# LoadCellAmplifierV2.net
KiCad netlist of a schematic drawn in Altium Designer
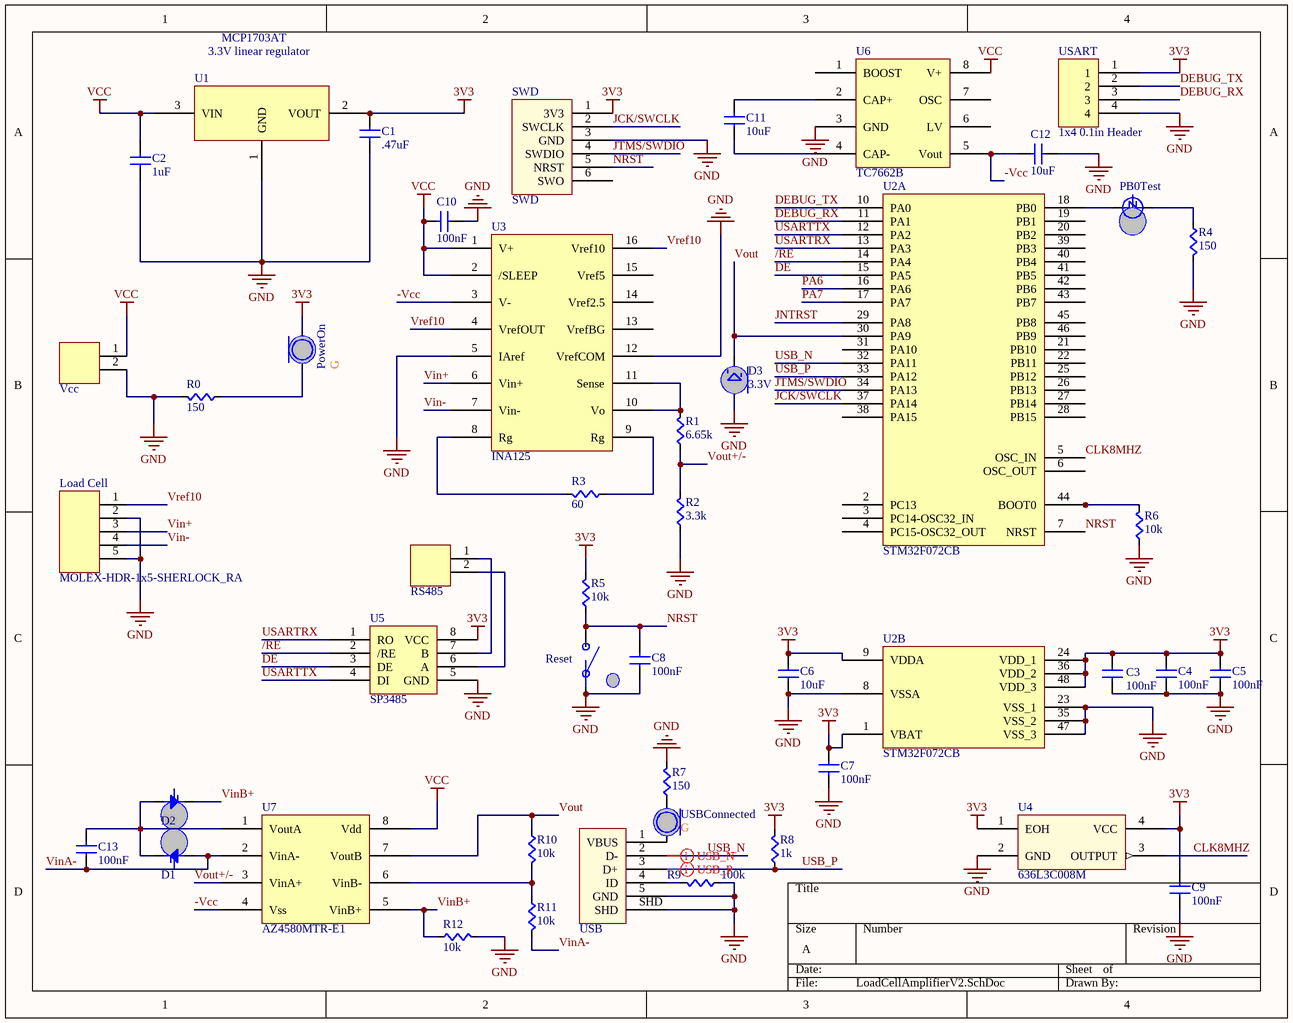
[diagram p0: LoadCellAmplifierV2.SchDoc]

(export (version "E")
  (design (tool "Eeschema 10.0.6"))
  (components
    (comp (ref "C1")
      (value ".47uF")
      (footprint "CAPC0603")
      (fields (field (name "Comment") "Cap"))
      (libsource (lib "SubjuGator8") (part "Cap"))
    )
    (comp (ref "C2")
      (value "1uF")
      (footprint "CAPC0603")
      (fields (field (name "Comment") "Cap"))
      (libsource (lib "SubjuGator8") (part "Cap"))
    )
    (comp (ref "C3")
      (value "100nF")
      (footprint "CAPC0603")
      (fields (field (name "Comment") "Cap"))
      (libsource (lib "SubjuGator8") (part "Cap"))
    )
    (comp (ref "C4")
      (value "100nF")
      (footprint "CAPC0603")
      (fields (field (name "Comment") "Cap"))
      (libsource (lib "SubjuGator8") (part "Cap"))
    )
    (comp (ref "C5")
      (value "100nF")
      (footprint "CAPC0603")
      (fields (field (name "Comment") "Cap"))
      (libsource (lib "SubjuGator8") (part "Cap"))
    )
    (comp (ref "C6")
      (value "10uF")
      (footprint "CAPC1206")
      (fields (field (name "Comment") "Cap"))
      (libsource (lib "SubjuGator8") (part "Cap"))
    )
    (comp (ref "C7")
      (value "100nF")
      (footprint "CAPC0603")
      (fields (field (name "Comment") "Cap"))
      (libsource (lib "SubjuGator8") (part "Cap"))
    )
    (comp (ref "C8")
      (value "100nF")
      (footprint "CAPC0603")
      (fields (field (name "Comment") "Cap"))
      (libsource (lib "SubjuGator8") (part "Cap"))
    )
    (comp (ref "C9")
      (value "100nF")
      (footprint "CAPC0603")
      (fields (field (name "Comment") "Cap"))
      (libsource (lib "SubjuGator8") (part "Cap"))
    )
    (comp (ref "C10")
      (value "100nF")
      (footprint "CAPC0603")
      (fields (field (name "Comment") "Cap"))
      (libsource (lib "SubjuGator8") (part "Cap"))
    )
    (comp (ref "C11")
      (value "10uF")
      (footprint "CAPC1206")
      (fields (field (name "Comment") "Cap"))
      (libsource (lib "SubjuGator8") (part "Cap"))
    )
    (comp (ref "C12")
      (value "10uF")
      (footprint "CAPC1206")
      (fields (field (name "Comment") "Cap"))
      (libsource (lib "SubjuGator8") (part "Cap"))
    )
    (comp (ref "C13")
      (value "100nF")
      (footprint "CAPC0603")
      (fields (field (name "Comment") "Cap"))
      (libsource (lib "SubjuGator8") (part "Cap"))
    )
    (comp (ref "D1")
      (value "Diode")
      (footprint "SOD-323F")
      (description "Standard Diode Template")
      (libsource (lib "SubjuGator8") (part "Diode"))
    )
    (comp (ref "D2")
      (value "Diode")
      (footprint "SOD-323F")
      (description "Standard Diode Template")
      (libsource (lib "") (part "Diode_1"))
    )
    (comp (ref "D3")
      (value "Zener")
      (footprint "LED0603")
      (description "Zener Diode")
      (fields (field (name "ZENER VOLTAGE") "3.3V"))
      (libsource (lib "SubjuGator8") (part "Zener"))
    )
    (comp (ref "Load Cell")
      (value "MOLEX-HDR-1x5-SHERLOCK_RA")
      (footprint "MOLEX-HDR-1X5-SHERLOCK- RA")
      (fields (field (name "MANUFACTURER PART NUMBER") "0353630560") (field (name "MANUFACTURER") "Molex"))
      (libsource (lib "SubjuGator8") (part "MOLEX-HDR-1x5-SHERLOCK_RA"))
    )
    (comp (ref "PB0Test")
      (value "LED")
      (footprint "LED0805")
      (fields (field (name "COLOR") "G"))
      (libsource (lib "SubjuGator8") (part "LED"))
    )
    (comp (ref "PowerOn")
      (value "LED")
      (footprint "LED0805")
      (fields (field (name "COLOR") "G"))
      (libsource (lib "") (part "LED_2"))
    )
    (comp (ref "R0")
      (value "150")
      (footprint "RES0603")
      (fields (field (name "Comment") "Res"))
      (libsource (lib "SubjuGator8") (part "Res"))
    )
    (comp (ref "R1")
      (value "6.65k")
      (footprint "RES0603")
      (fields (field (name "Comment") "Res"))
      (libsource (lib "SubjuGator8") (part "Res"))
    )
    (comp (ref "R2")
      (value "3.3k")
      (footprint "RES0603")
      (fields (field (name "Comment") "Res"))
      (libsource (lib "SubjuGator8") (part "Res"))
    )
    (comp (ref "R3")
      (value "60")
      (footprint "RES0603")
      (fields (field (name "Comment") "Res"))
      (libsource (lib "SubjuGator8") (part "Res"))
    )
    (comp (ref "R4")
      (value "150")
      (footprint "RES0603")
      (fields (field (name "Comment") "Res"))
      (libsource (lib "SubjuGator8") (part "Res"))
    )
    (comp (ref "R5")
      (value "10k")
      (footprint "RES0603")
      (fields (field (name "Comment") "Res"))
      (libsource (lib "SubjuGator8") (part "Res"))
    )
    (comp (ref "R6")
      (value "10k")
      (footprint "RES0603")
      (fields (field (name "Comment") "Res"))
      (libsource (lib "SubjuGator8") (part "Res"))
    )
    (comp (ref "R7")
      (value "150")
      (footprint "RES0603")
      (fields (field (name "Comment") "Res"))
      (libsource (lib "SubjuGator8") (part "Res"))
    )
    (comp (ref "R8")
      (value "1k")
      (footprint "RES0603")
      (fields (field (name "Comment") "Res"))
      (libsource (lib "SubjuGator8") (part "Res"))
    )
    (comp (ref "R9")
      (value "100k")
      (footprint "RES0603")
      (fields (field (name "Comment") "Res"))
      (libsource (lib "SubjuGator8") (part "Res"))
    )
    (comp (ref "R10")
      (value "10k")
      (footprint "RES0603")
      (fields (field (name "Comment") "Res"))
      (libsource (lib "SubjuGator8") (part "Res"))
    )
    (comp (ref "R11")
      (value "10k")
      (footprint "RES0603")
      (fields (field (name "Comment") "Res"))
      (libsource (lib "SubjuGator8") (part "Res"))
    )
    (comp (ref "R12")
      (value "10k")
      (footprint "RES0603")
      (fields (field (name "Comment") "Res"))
      (libsource (lib "SubjuGator8") (part "Res"))
    )
    (comp (ref "Reset")
      (value "Button")
      (footprint "PTS645xxxxSMTR92")
      (description "SPST Button")
      (libsource (lib "SubjuGator8") (part "Button"))
    )
    (comp (ref "RS485")
      (value "2-pin Horz Sherlock")
      (footprint "MOLEX-HDR-1X2-SHERLOCK-HORZ")
      (fields
        (field (name "MANUFACTURER PART NUMBER") "0353630260")
        (field (name "MANUFACTURER") "Molex Inc")
      )
      (libsource (lib "SubjuGator8") (part "MOLEX-HDR-1x2-SHERLOCK_RA"))
    )
    (comp (ref "SWD")
      (value "SWD")
      (footprint "SWD_STM32")
      (description "SWD connector matching the pinout on STM Discovery Boards")
      (libsource (lib "SubjuGator8") (part "SWD_STM32"))
    )
    (comp (ref "U1")
      (value "MCP1703AT")
      (footprint "MCP1703AT-xx02EDB")
      (description "250 mA, 16V, Low Quiescent Current LDO Regulator")
      (libsource (lib "SubjuGator8") (part "MCP1703AT"))
    )
    (comp (ref "U2")
      (value "STM32F072CB")
      (footprint "STM32F072CB")
      (description "MCU 32BIT 128KB FLASH 48LQFP")
      (libsource (lib "ICs") (part "STM32F072CB"))
    )
    (comp (ref "U3")
      (value "INA125")
      (footprint "SOIC127P600X175-16N")
      (description "Instrumentation Amplifier")
      (libsource (lib "ICs") (part "INA125"))
    )
    (comp (ref "U4")
      (value "636L3C008M")
      (footprint "636L3C")
      (description "HCMOS/TTL Clock Oscillator")
      (libsource (lib "SubjuGator8") (part "636L3C"))
    )
    (comp (ref "U5")
      (value "SP3485")
      (footprint "SP3485")
      (description "IC TXRX RS485 HALF DUPLEX 8NSOIC")
      (libsource (lib "SubjuGator8") (part "SP3485"))
    )
    (comp (ref "U6")
      (value "TC7662B")
      (footprint "8-SOIC")
      (description "Charge Pump DC to DC Voltage Converter")
      (libsource (lib "SubjuGator8") (part "TC7662B"))
    )
    (comp (ref "U7")
      (value "AZ4580MTR-E1")
      (footprint "8-SOIC")
      (description "IC OPAMP GEN PURP SO-8")
      (libsource (lib "SubjuGator8") (part "AZ4580MTR-E1"))
    )
    (comp (ref "USART")
      (value "1x4 0.1in Header")
      (footprint "1x4 0.1in Header")
      (libsource (lib "SubjuGator8") (part "1x4 0.1in Header"))
    )
    (comp (ref "USB")
      (value "USB Micro")
      (footprint "10118192-0001LF")
      (description "USB Mini B Metal Shield SMT")
      (libsource (lib "SubjuGator8") (part "USB Micro"))
    )
    (comp (ref "USBConnected")
      (value "LED")
      (footprint "LED0805")
      (fields (field (name "COLOR") "G"))
      (libsource (lib "") (part "LED_1"))
    )
    (comp (ref "Vcc")
      (value "2-pin Horz Sherlock")
      (footprint "MOLEX-HDR-1X2-SHERLOCK-HORZ")
      (fields
        (field (name "MANUFACTURER PART NUMBER") "0353630260")
        (field (name "MANUFACTURER") "Molex Inc")
      )
      (libsource (lib "SubjuGator8") (part "MOLEX-HDR-1x2-SHERLOCK_RA"))
    )
  )
  (nets
    (net (code "1") (name "/-Vcc") (class "Default")
      (node (ref "C12") (pin "2") (pinfunction "B_2") (pintype "passive"))
      (node (ref "U3") (pin "3") (pinfunction "V-_3") (pintype "passive"))
      (node (ref "U6") (pin "5") (pinfunction "Vout_5") (pintype "passive"))
      (node (ref "U7") (pin "4") (pinfunction "Vss_4") (pintype "passive"))
    )
    (net (code "2") (name "/CLK8MHZ") (class "Default")
      (node (ref "U2") (pin "5") (pinfunction "OSC_IN_5") (pintype "passive"))
      (node (ref "U4") (pin "3") (pinfunction "OUTPUT_3") (pintype "output"))
    )
    (net (code "3") (name "/DE") (class "Default")
      (node (ref "U2") (pin "15") (pinfunction "PA5_15") (pintype "passive"))
      (node (ref "U5") (pin "3") (pinfunction "DE_3") (pintype "passive"))
    )
    (net (code "4") (name "/DEBUG_RX") (class "Default")
      (node (ref "U2") (pin "11") (pinfunction "PA1_11") (pintype "passive"))
      (node (ref "USART") (pin "3") (pinfunction "3_3") (pintype "passive"))
    )
    (net (code "5") (name "/DEBUG_TX") (class "Default")
      (node (ref "U2") (pin "10") (pinfunction "PA0_10") (pintype "passive"))
      (node (ref "USART") (pin "2") (pinfunction "2_2") (pintype "passive"))
    )
    (net (code "6") (name "/JCK{slash}SWCLK") (class "Default")
      (node (ref "SWD") (pin "2") (pinfunction "SWCLK_2") (pintype "passive"))
      (node (ref "U2") (pin "37") (pinfunction "PA14_37") (pintype "passive"))
    )
    (net (code "7") (name "/JNTRST") (class "Default")
      (node (ref "U2") (pin "29") (pinfunction "PA8_29") (pintype "passive"))
    )
    (net (code "8") (name "/JTMS{slash}SWDIO") (class "Default")
      (node (ref "SWD") (pin "4") (pinfunction "SWDIO_4") (pintype "passive"))
      (node (ref "U2") (pin "34") (pinfunction "PA13_34") (pintype "passive"))
    )
    (net (code "9") (name "/NRST") (class "Default")
      (node (ref "C8") (pin "1") (pinfunction "A_1") (pintype "passive"))
      (node (ref "R5") (pin "2") (pinfunction "B_2") (pintype "passive"))
      (node (ref "Reset") (pin "B") (pinfunction "B_B") (pintype "passive"))
      (node (ref "SWD") (pin "5") (pinfunction "NRST_5") (pintype "passive"))
      (node (ref "U2") (pin "7") (pinfunction "NRST_7") (pintype "passive"))
    )
    (net (code "10") (name "/PA6") (class "Default")
      (node (ref "U2") (pin "16") (pinfunction "PA6_16") (pintype "passive"))
    )
    (net (code "11") (name "/PA7") (class "Default")
      (node (ref "U2") (pin "17") (pinfunction "PA7_17") (pintype "passive"))
    )
    (net (code "12") (name "/USARTRX") (class "Default")
      (node (ref "U2") (pin "13") (pinfunction "PA3_13") (pintype "passive"))
      (node (ref "U5") (pin "1") (pinfunction "RO_1") (pintype "passive"))
    )
    (net (code "13") (name "/USARTTX") (class "Default")
      (node (ref "U2") (pin "12") (pinfunction "PA2_12") (pintype "passive"))
      (node (ref "U5") (pin "4") (pinfunction "DI_4") (pintype "passive"))
    )
    (net (code "14") (name "/USB_N") (class "Default")
      (node (ref "U2") (pin "32") (pinfunction "PA11_32") (pintype "passive"))
      (node (ref "USB") (pin "2") (pinfunction "D-_2") (pintype "passive"))
    )
    (net (code "15") (name "/USB_P") (class "Default")
      (node (ref "R8") (pin "2") (pinfunction "B_2") (pintype "passive"))
      (node (ref "U2") (pin "33") (pinfunction "PA12_33") (pintype "passive"))
      (node (ref "USB") (pin "3") (pinfunction "D+_3") (pintype "passive"))
    )
    (net (code "16") (name "/Vin+") (class "Default")
      (node (ref "Load Cell") (pin "3") (pinfunction "3_3") (pintype "passive"))
      (node (ref "U3") (pin "6") (pinfunction "Vin+_6") (pintype "passive"))
    )
    (net (code "17") (name "/Vin-") (class "Default")
      (node (ref "Load Cell") (pin "4") (pinfunction "4_4") (pintype "passive"))
      (node (ref "U3") (pin "7") (pinfunction "Vin-_7") (pintype "passive"))
    )
    (net (code "18") (name "/VinA-") (class "Default")
      (node (ref "C13") (pin "2") (pinfunction "B_2") (pintype "passive"))
      (node (ref "D1") (pin "A") (pinfunction "A_A") (pintype "passive"))
      (node (ref "R11") (pin "1") (pinfunction "A_1") (pintype "passive"))
      (node (ref "U7") (pin "2") (pinfunction "VinA-_2") (pintype "passive"))
    )
    (net (code "19") (name "/VinB+") (class "Default")
      (node (ref "D2") (pin "C") (pinfunction "C_C") (pintype "passive"))
      (node (ref "R12") (pin "2") (pinfunction "B_2") (pintype "passive"))
      (node (ref "U7") (pin "5") (pinfunction "VinB+_5") (pintype "passive"))
    )
    (net (code "20") (name "/Vout") (class "Default")
      (node (ref "D3") (pin "C") (pinfunction "C_C") (pintype "passive"))
      (node (ref "R10") (pin "2") (pinfunction "B_2") (pintype "passive"))
      (node (ref "U2") (pin "30") (pinfunction "PA9_30") (pintype "passive"))
      (node (ref "U7") (pin "7") (pinfunction "VoutB_7") (pintype "passive"))
    )
    (net (code "21") (name "/Vout+{slash}-") (class "Default")
      (node (ref "R1") (pin "2") (pinfunction "B_2") (pintype "passive"))
      (node (ref "R2") (pin "1") (pinfunction "A_1") (pintype "passive"))
      (node (ref "U7") (pin "3") (pinfunction "VinA+_3") (pintype "passive"))
    )
    (net (code "22") (name "/Vref10") (class "Default")
      (node (ref "Load Cell") (pin "1") (pinfunction "1_1") (pintype "passive"))
      (node (ref "U3") (pin "16") (pinfunction "Vref10_16") (pintype "passive"))
      (node (ref "U3") (pin "4") (pinfunction "VrefOUT_4") (pintype "passive"))
    )
    (net (code "23") (name "/{slash}RE") (class "Default")
      (node (ref "U2") (pin "14") (pinfunction "PA4_14") (pintype "passive"))
      (node (ref "U5") (pin "2") (pinfunction "/RE_2") (pintype "passive"))
    )
    (net (code "24") (name "3V3") (class "Default")
      (node (ref "C1") (pin "1") (pinfunction "A_1") (pintype "passive"))
      (node (ref "C3") (pin "1") (pinfunction "A_1") (pintype "passive"))
      (node (ref "C4") (pin "1") (pinfunction "A_1") (pintype "passive"))
      (node (ref "C5") (pin "1") (pinfunction "A_1") (pintype "passive"))
      (node (ref "C6") (pin "2") (pinfunction "B_2") (pintype "passive"))
      (node (ref "C7") (pin "1") (pinfunction "A_1") (pintype "passive"))
      (node (ref "C9") (pin "1") (pinfunction "A_1") (pintype "passive"))
      (node (ref "PowerOn") (pin "A") (pinfunction "A_A") (pintype "passive"))
      (node (ref "R5") (pin "1") (pinfunction "A_1") (pintype "passive"))
      (node (ref "R8") (pin "1") (pinfunction "A_1") (pintype "passive"))
      (node (ref "SWD") (pin "1") (pinfunction "3V3_1") (pintype "passive"))
      (node (ref "U1") (pin "2") (pinfunction "VOUT_2") (pintype "passive"))
      (node (ref "U2") (pin "1") (pinfunction "VBAT_1") (pintype "passive"))
      (node (ref "U2") (pin "24") (pinfunction "VDD_1_24") (pintype "passive"))
      (node (ref "U2") (pin "36") (pinfunction "VDD_2_36") (pintype "passive"))
      (node (ref "U2") (pin "48") (pinfunction "VDD_3_48") (pintype "passive"))
      (node (ref "U2") (pin "9") (pinfunction "VDDA_9") (pintype "passive"))
      (node (ref "U4") (pin "1") (pinfunction "EOH_1") (pintype "passive"))
      (node (ref "U4") (pin "4") (pinfunction "VCC_4") (pintype "power_in"))
      (node (ref "U5") (pin "8") (pinfunction "VCC_8") (pintype "passive"))
      (node (ref "USART") (pin "1") (pinfunction "1_1") (pintype "passive"))
    )
    (net (code "25") (name "GND") (class "Default")
      (node (ref "C1") (pin "2") (pinfunction "B_2") (pintype "passive"))
      (node (ref "C10") (pin "1") (pinfunction "A_1") (pintype "passive"))
      (node (ref "C12") (pin "1") (pinfunction "A_1") (pintype "passive"))
      (node (ref "C2") (pin "2") (pinfunction "B_2") (pintype "passive"))
      (node (ref "C3") (pin "2") (pinfunction "B_2") (pintype "passive"))
      (node (ref "C4") (pin "2") (pinfunction "B_2") (pintype "passive"))
      (node (ref "C5") (pin "2") (pinfunction "B_2") (pintype "passive"))
      (node (ref "C6") (pin "1") (pinfunction "A_1") (pintype "passive"))
      (node (ref "C7") (pin "2") (pinfunction "B_2") (pintype "passive"))
      (node (ref "C8") (pin "2") (pinfunction "B_2") (pintype "passive"))
      (node (ref "C9") (pin "2") (pinfunction "B_2") (pintype "passive"))
      (node (ref "D3") (pin "A") (pinfunction "A_A") (pintype "passive"))
      (node (ref "Load Cell") (pin "2") (pinfunction "2_2") (pintype "passive"))
      (node (ref "Load Cell") (pin "5") (pinfunction "5_5") (pintype "passive"))
      (node (ref "R0") (pin "1") (pinfunction "A_1") (pintype "passive"))
      (node (ref "R12") (pin "1") (pinfunction "A_1") (pintype "passive"))
      (node (ref "R2") (pin "2") (pinfunction "B_2") (pintype "passive"))
      (node (ref "R4") (pin "1") (pinfunction "A_1") (pintype "passive"))
      (node (ref "R6") (pin "2") (pinfunction "B_2") (pintype "passive"))
      (node (ref "R7") (pin "1") (pinfunction "A_1") (pintype "passive"))
      (node (ref "R9") (pin "2") (pinfunction "B_2") (pintype "passive"))
      (node (ref "Reset") (pin "A") (pinfunction "A_A") (pintype "passive"))
      (node (ref "SWD") (pin "3") (pinfunction "GND_3") (pintype "passive"))
      (node (ref "U1") (pin "1") (pinfunction "GND_1") (pintype "power_in"))
      (node (ref "U2") (pin "23") (pinfunction "VSS_1_23") (pintype "passive"))
      (node (ref "U2") (pin "35") (pinfunction "VSS_2_35") (pintype "passive"))
      (node (ref "U2") (pin "47") (pinfunction "VSS_3_47") (pintype "passive"))
      (node (ref "U2") (pin "8") (pinfunction "VSSA_8") (pintype "passive"))
      (node (ref "U3") (pin "12") (pinfunction "VrefCOM_12") (pintype "passive"))
      (node (ref "U3") (pin "5") (pinfunction "IAref_5") (pintype "passive"))
      (node (ref "U4") (pin "2") (pinfunction "GND_2") (pintype "power_in"))
      (node (ref "U5") (pin "5") (pinfunction "GND_5") (pintype "passive"))
      (node (ref "U6") (pin "3") (pinfunction "GND_3") (pintype "passive"))
      (node (ref "USART") (pin "4") (pinfunction "4_4") (pintype "passive"))
      (node (ref "USB") (pin "5") (pinfunction "GND_5") (pintype "passive"))
      (node (ref "USB") (pin "SHD") (pinfunction "SHD_SHD") (pintype "passive"))
      (node (ref "Vcc") (pin "2") (pinfunction "2_2") (pintype "passive"))
    )
    (net (code "26") (name "Net-(C11-A)") (class "Default")
      (node (ref "C11") (pin "1") (pinfunction "A_1") (pintype "passive"))
      (node (ref "U6") (pin "4") (pinfunction "CAP-_4") (pintype "passive"))
    )
    (net (code "27") (name "Net-(C11-B)") (class "Default")
      (node (ref "C11") (pin "2") (pinfunction "B_2") (pintype "passive"))
      (node (ref "U6") (pin "2") (pinfunction "CAP+_2") (pintype "passive"))
    )
    (net (code "28") (name "Net-(C13-A)") (class "Default")
      (node (ref "C13") (pin "1") (pinfunction "A_1") (pintype "passive"))
      (node (ref "D1") (pin "C") (pinfunction "C_C") (pintype "passive"))
      (node (ref "D2") (pin "A") (pinfunction "A_A") (pintype "passive"))
      (node (ref "U7") (pin "1") (pinfunction "VoutA_1") (pintype "passive"))
    )
    (net (code "29") (name "Net-(R0-B)") (class "Default")
      (node (ref "PowerOn") (pin "C") (pinfunction "C_C") (pintype "passive"))
      (node (ref "R0") (pin "2") (pinfunction "B_2") (pintype "passive"))
    )
    (net (code "30") (name "Net-(R1-A)") (class "Default")
      (node (ref "R1") (pin "1") (pinfunction "A_1") (pintype "passive"))
      (node (ref "U3") (pin "10") (pinfunction "Vo_10") (pintype "passive"))
      (node (ref "U3") (pin "11") (pinfunction "Sense_11") (pintype "passive"))
    )
    (net (code "31") (name "Net-(R3-A)") (class "Default")
      (node (ref "R3") (pin "1") (pinfunction "A_1") (pintype "passive"))
      (node (ref "U3") (pin "8") (pinfunction "Rg_8") (pintype "passive"))
    )
    (net (code "32") (name "Net-(R3-B)") (class "Default")
      (node (ref "R3") (pin "2") (pinfunction "B_2") (pintype "passive"))
      (node (ref "U3") (pin "9") (pinfunction "Rg_9") (pintype "passive"))
    )
    (net (code "33") (name "Net-(R4-B)") (class "Default")
      (node (ref "PB0Test") (pin "C") (pinfunction "C_C") (pintype "passive"))
      (node (ref "R4") (pin "2") (pinfunction "B_2") (pintype "passive"))
    )
    (net (code "34") (name "Net-(R6-A)") (class "Default")
      (node (ref "R6") (pin "1") (pinfunction "A_1") (pintype "passive"))
      (node (ref "U2") (pin "44") (pinfunction "BOOT0_44") (pintype "passive"))
    )
    (net (code "35") (name "Net-(R7-B)") (class "Default")
      (node (ref "R7") (pin "2") (pinfunction "B_2") (pintype "passive"))
      (node (ref "USBConnected") (pin "C") (pinfunction "C_C") (pintype "passive"))
    )
    (net (code "36") (name "Net-(R9-A)") (class "Default")
      (node (ref "R9") (pin "1") (pinfunction "A_1") (pintype "passive"))
      (node (ref "USB") (pin "4") (pinfunction "ID_4") (pintype "passive"))
    )
    (net (code "37") (name "Net-(R10-A)") (class "Default")
      (node (ref "R10") (pin "1") (pinfunction "A_1") (pintype "passive"))
      (node (ref "R11") (pin "2") (pinfunction "B_2") (pintype "passive"))
      (node (ref "U7") (pin "6") (pinfunction "VinB-_6") (pintype "passive"))
    )
    (net (code "38") (name "Net-(U2A-PB0)") (class "Default")
      (node (ref "PB0Test") (pin "A") (pinfunction "A_A") (pintype "passive"))
      (node (ref "U2") (pin "18") (pinfunction "PB0_18") (pintype "passive"))
    )
    (net (code "39") (name "Net-(U5-A)") (class "Default")
      (node (ref "RS485") (pin "2") (pinfunction "2_2") (pintype "passive"))
      (node (ref "U5") (pin "6") (pinfunction "A_6") (pintype "passive"))
    )
    (net (code "40") (name "Net-(U5-B)") (class "Default")
      (node (ref "RS485") (pin "1") (pinfunction "1_1") (pintype "passive"))
      (node (ref "U5") (pin "7") (pinfunction "B_7") (pintype "passive"))
    )
    (net (code "41") (name "Net-(USB-VBUS)") (class "Default")
      (node (ref "USB") (pin "1") (pinfunction "VBUS_1") (pintype "passive"))
      (node (ref "USBConnected") (pin "A") (pinfunction "A_A") (pintype "passive"))
    )
    (net (code "42") (name "VCC") (class "Default")
      (node (ref "C10") (pin "2") (pinfunction "B_2") (pintype "passive"))
      (node (ref "C2") (pin "1") (pinfunction "A_1") (pintype "passive"))
      (node (ref "U1") (pin "3") (pinfunction "VIN_3") (pintype "passive"))
      (node (ref "U3") (pin "1") (pinfunction "V+_1") (pintype "passive"))
      (node (ref "U3") (pin "2") (pinfunction "/SLEEP_2") (pintype "passive"))
      (node (ref "U6") (pin "8") (pinfunction "V+_8") (pintype "passive"))
      (node (ref "U7") (pin "8") (pinfunction "Vdd_8") (pintype "passive"))
      (node (ref "Vcc") (pin "1") (pinfunction "1_1") (pintype "passive"))
    )
    (net (code "43") (name "unconnected-(SWD-SWO-Pad6)") (class "Default")
      (node (ref "SWD") (pin "6") (pinfunction "SWO_6") (pintype "passive"))
    )
    (net (code "44") (name "unconnected-(U2A-OSC_OUT-Pad6)") (class "Default")
      (node (ref "U2") (pin "6") (pinfunction "OSC_OUT_6") (pintype "passive"))
    )
    (net (code "45") (name "unconnected-(U2A-PA10-Pad31)") (class "Default")
      (node (ref "U2") (pin "31") (pinfunction "PA10_31") (pintype "passive"))
    )
    (net (code "46") (name "unconnected-(U2A-PA15-Pad38)") (class "Default")
      (node (ref "U2") (pin "38") (pinfunction "PA15_38") (pintype "passive"))
    )
    (net (code "47") (name "unconnected-(U2A-PB1-Pad19)") (class "Default")
      (node (ref "U2") (pin "19") (pinfunction "PB1_19") (pintype "passive"))
    )
    (net (code "48") (name "unconnected-(U2A-PB2-Pad20)") (class "Default")
      (node (ref "U2") (pin "20") (pinfunction "PB2_20") (pintype "passive"))
    )
    (net (code "49") (name "unconnected-(U2A-PB3-Pad39)") (class "Default")
      (node (ref "U2") (pin "39") (pinfunction "PB3_39") (pintype "passive"))
    )
    (net (code "50") (name "unconnected-(U2A-PB4-Pad40)") (class "Default")
      (node (ref "U2") (pin "40") (pinfunction "PB4_40") (pintype "passive"))
    )
    (net (code "51") (name "unconnected-(U2A-PB5-Pad41)") (class "Default")
      (node (ref "U2") (pin "41") (pinfunction "PB5_41") (pintype "passive"))
    )
    (net (code "52") (name "unconnected-(U2A-PB6-Pad42)") (class "Default")
      (node (ref "U2") (pin "42") (pinfunction "PB6_42") (pintype "passive"))
    )
    (net (code "53") (name "unconnected-(U2A-PB7-Pad43)") (class "Default")
      (node (ref "U2") (pin "43") (pinfunction "PB7_43") (pintype "passive"))
    )
    (net (code "54") (name "unconnected-(U2A-PB8-Pad45)") (class "Default")
      (node (ref "U2") (pin "45") (pinfunction "PB8_45") (pintype "passive"))
    )
    (net (code "55") (name "unconnected-(U2A-PB9-Pad46)") (class "Default")
      (node (ref "U2") (pin "46") (pinfunction "PB9_46") (pintype "passive"))
    )
    (net (code "56") (name "unconnected-(U2A-PB10-Pad21)") (class "Default")
      (node (ref "U2") (pin "21") (pinfunction "PB10_21") (pintype "passive"))
    )
    (net (code "57") (name "unconnected-(U2A-PB11-Pad22)") (class "Default")
      (node (ref "U2") (pin "22") (pinfunction "PB11_22") (pintype "passive"))
    )
    (net (code "58") (name "unconnected-(U2A-PB12-Pad25)") (class "Default")
      (node (ref "U2") (pin "25") (pinfunction "PB12_25") (pintype "passive"))
    )
    (net (code "59") (name "unconnected-(U2A-PB13-Pad26)") (class "Default")
      (node (ref "U2") (pin "26") (pinfunction "PB13_26") (pintype "passive"))
    )
    (net (code "60") (name "unconnected-(U2A-PB14-Pad27)") (class "Default")
      (node (ref "U2") (pin "27") (pinfunction "PB14_27") (pintype "passive"))
    )
    (net (code "61") (name "unconnected-(U2A-PB15-Pad28)") (class "Default")
      (node (ref "U2") (pin "28") (pinfunction "PB15_28") (pintype "passive"))
    )
    (net (code "62") (name "unconnected-(U2A-PC13-Pad2)") (class "Default")
      (node (ref "U2") (pin "2") (pinfunction "PC13_2") (pintype "passive"))
    )
    (net (code "63") (name "unconnected-(U2A-PC14-OSC32_IN-Pad3)") (class "Default")
      (node (ref "U2") (pin "3") (pinfunction "PC14-OSC32_IN_3") (pintype "passive"))
    )
    (net (code "64") (name "unconnected-(U2A-PC15-OSC32_OUT-Pad4)") (class "Default")
      (node (ref "U2") (pin "4") (pinfunction "PC15-OSC32_OUT_4") (pintype "passive"))
    )
    (net (code "65") (name "unconnected-(U3-Vref2.5-Pad14)") (class "Default")
      (node (ref "U3") (pin "14") (pinfunction "Vref2.5_14") (pintype "passive"))
    )
    (net (code "66") (name "unconnected-(U3-Vref5-Pad15)") (class "Default")
      (node (ref "U3") (pin "15") (pinfunction "Vref5_15") (pintype "passive"))
    )
    (net (code "67") (name "unconnected-(U3-VrefBG-Pad13)") (class "Default")
      (node (ref "U3") (pin "13") (pinfunction "VrefBG_13") (pintype "passive"))
    )
    (net (code "68") (name "unconnected-(U6-BOOST-Pad1)") (class "Default")
      (node (ref "U6") (pin "1") (pinfunction "BOOST_1") (pintype "passive"))
    )
    (net (code "69") (name "unconnected-(U6-LV-Pad6)") (class "Default")
      (node (ref "U6") (pin "6") (pinfunction "LV_6") (pintype "passive"))
    )
    (net (code "70") (name "unconnected-(U6-OSC-Pad7)") (class "Default")
      (node (ref "U6") (pin "7") (pinfunction "OSC_7") (pintype "passive"))
    )
  )
)
